# Rail.net
KiCad netlist of a schematic drawn in Altium Designer
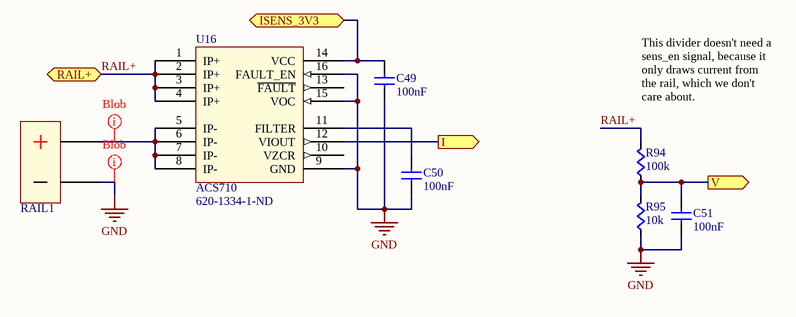
[diagram p0: Rail.SchDoc]

(export (version "E")
  (design (tool "Eeschema 10.0.6"))
  (components
    (comp (ref "C49")
      (value "100nF")
      (footprint "CAPC0603")
      (fields (field (name "Comment") "Cap"))
      (libsource (lib "SubjuGator8") (part "Cap"))
    )
    (comp (ref "C50")
      (value "100nF")
      (footprint "CAPC0603")
      (fields (field (name "Comment") "Cap"))
      (libsource (lib "SubjuGator8") (part "Cap"))
    )
    (comp (ref "C51")
      (value "100nF")
      (footprint "CAPC0603")
      (fields (field (name "Comment") "Cap"))
      (libsource (lib "SubjuGator8") (part "Cap"))
    )
    (comp (ref "R94")
      (value "100k")
      (footprint "RES0603")
      (fields (field (name "Comment") "Res"))
      (libsource (lib "SubjuGator8") (part "Res"))
    )
    (comp (ref "R95")
      (value "10k")
      (footprint "RES0603")
      (fields (field (name "Comment") "Res"))
      (libsource (lib "SubjuGator8") (part "Res"))
    )
    (comp (ref "RAIL1")
      (value "BATWIRE")
      (footprint "BATWIRE12")
      (description "Two large gauge leads soldered directly to the board.")
      (libsource (lib "SubjuGator8") (part "BATWIRE"))
    )
    (comp (ref "U16")
      (value "ACS710")
      (footprint "ACS710")
      (description "Current Sensor with Integrated Overcurrent Detection")
      (fields (field (name "SUPPLIER PART NUMBER 1") "620-1334-1-ND"))
      (libsource (lib "SubjuGator8") (part "ACS710"))
    )
  )
  (nets
    (net (code "1") (name "/I") (class "Default")
      (node (ref "U16") (pin "12") (pinfunction "VIOUT_12") (pintype "output"))
    )
    (net (code "2") (name "/ISENS_3V3") (class "Default")
      (node (ref "C49") (pin "1") (pinfunction "A_1") (pintype "passive"))
      (node (ref "U16") (pin "14") (pinfunction "VCC_14") (pintype "power_in"))
    )
    (net (code "3") (name "/RAIL+") (class "Default")
      (node (ref "R94") (pin "1") (pinfunction "A_1") (pintype "passive"))
      (node (ref "U16") (pin "1") (pinfunction "IP+_1") (pintype "passive"))
      (node (ref "U16") (pin "2") (pinfunction "IP+_2") (pintype "passive"))
      (node (ref "U16") (pin "3") (pinfunction "IP+_3") (pintype "passive"))
      (node (ref "U16") (pin "4") (pinfunction "IP+_4") (pintype "passive"))
    )
    (net (code "4") (name "/V") (class "Default")
      (node (ref "C51") (pin "1") (pinfunction "A_1") (pintype "passive"))
      (node (ref "R94") (pin "2") (pinfunction "B_2") (pintype "passive"))
      (node (ref "R95") (pin "1") (pinfunction "A_1") (pintype "passive"))
    )
    (net (code "5") (name "GND") (class "Default")
      (node (ref "C49") (pin "2") (pinfunction "B_2") (pintype "passive"))
      (node (ref "C50") (pin "2") (pinfunction "B_2") (pintype "passive"))
      (node (ref "C51") (pin "2") (pinfunction "B_2") (pintype "passive"))
      (node (ref "R95") (pin "2") (pinfunction "B_2") (pintype "passive"))
      (node (ref "RAIL1") (pin "-") (pinfunction "-_-") (pintype "power_in"))
      (node (ref "U16") (pin "15") (pinfunction "VOC_15") (pintype "input"))
      (node (ref "U16") (pin "16") (pinfunction "FAULT_EN_16") (pintype "input"))
      (node (ref "U16") (pin "9") (pinfunction "GND_9") (pintype "power_in"))
    )
    (net (code "6") (name "Net-(C50-A)") (class "Default")
      (node (ref "C50") (pin "1") (pinfunction "A_1") (pintype "passive"))
      (node (ref "U16") (pin "11") (pinfunction "FILTER_11") (pintype "passive"))
    )
    (net (code "7") (name "Net-(RAIL1-Pad+)") (class "Default")
      (node (ref "RAIL1") (pin "+") (pinfunction "+_+") (pintype "power_in"))
      (node (ref "U16") (pin "5") (pinfunction "IP-_5") (pintype "passive"))
      (node (ref "U16") (pin "6") (pinfunction "IP-_6") (pintype "passive"))
      (node (ref "U16") (pin "7") (pinfunction "IP-_7") (pintype "passive"))
      (node (ref "U16") (pin "8") (pinfunction "IP-_8") (pintype "passive"))
    )
    (net (code "8") (name "unconnected-(U16-VZCR-Pad10)") (class "Default")
      (node (ref "U16") (pin "10") (pinfunction "VZCR_10") (pintype "output"))
    )
    (net (code "9") (name "unconnected-(U16-~{FAULT}-Pad13)") (class "Default")
      (node (ref "U16") (pin "13") (pinfunction "~{FAULT}_13") (pintype "output"))
    )
  )
)
